# Supply_switch.net
KiCad netlist of a schematic drawn in EAGLE
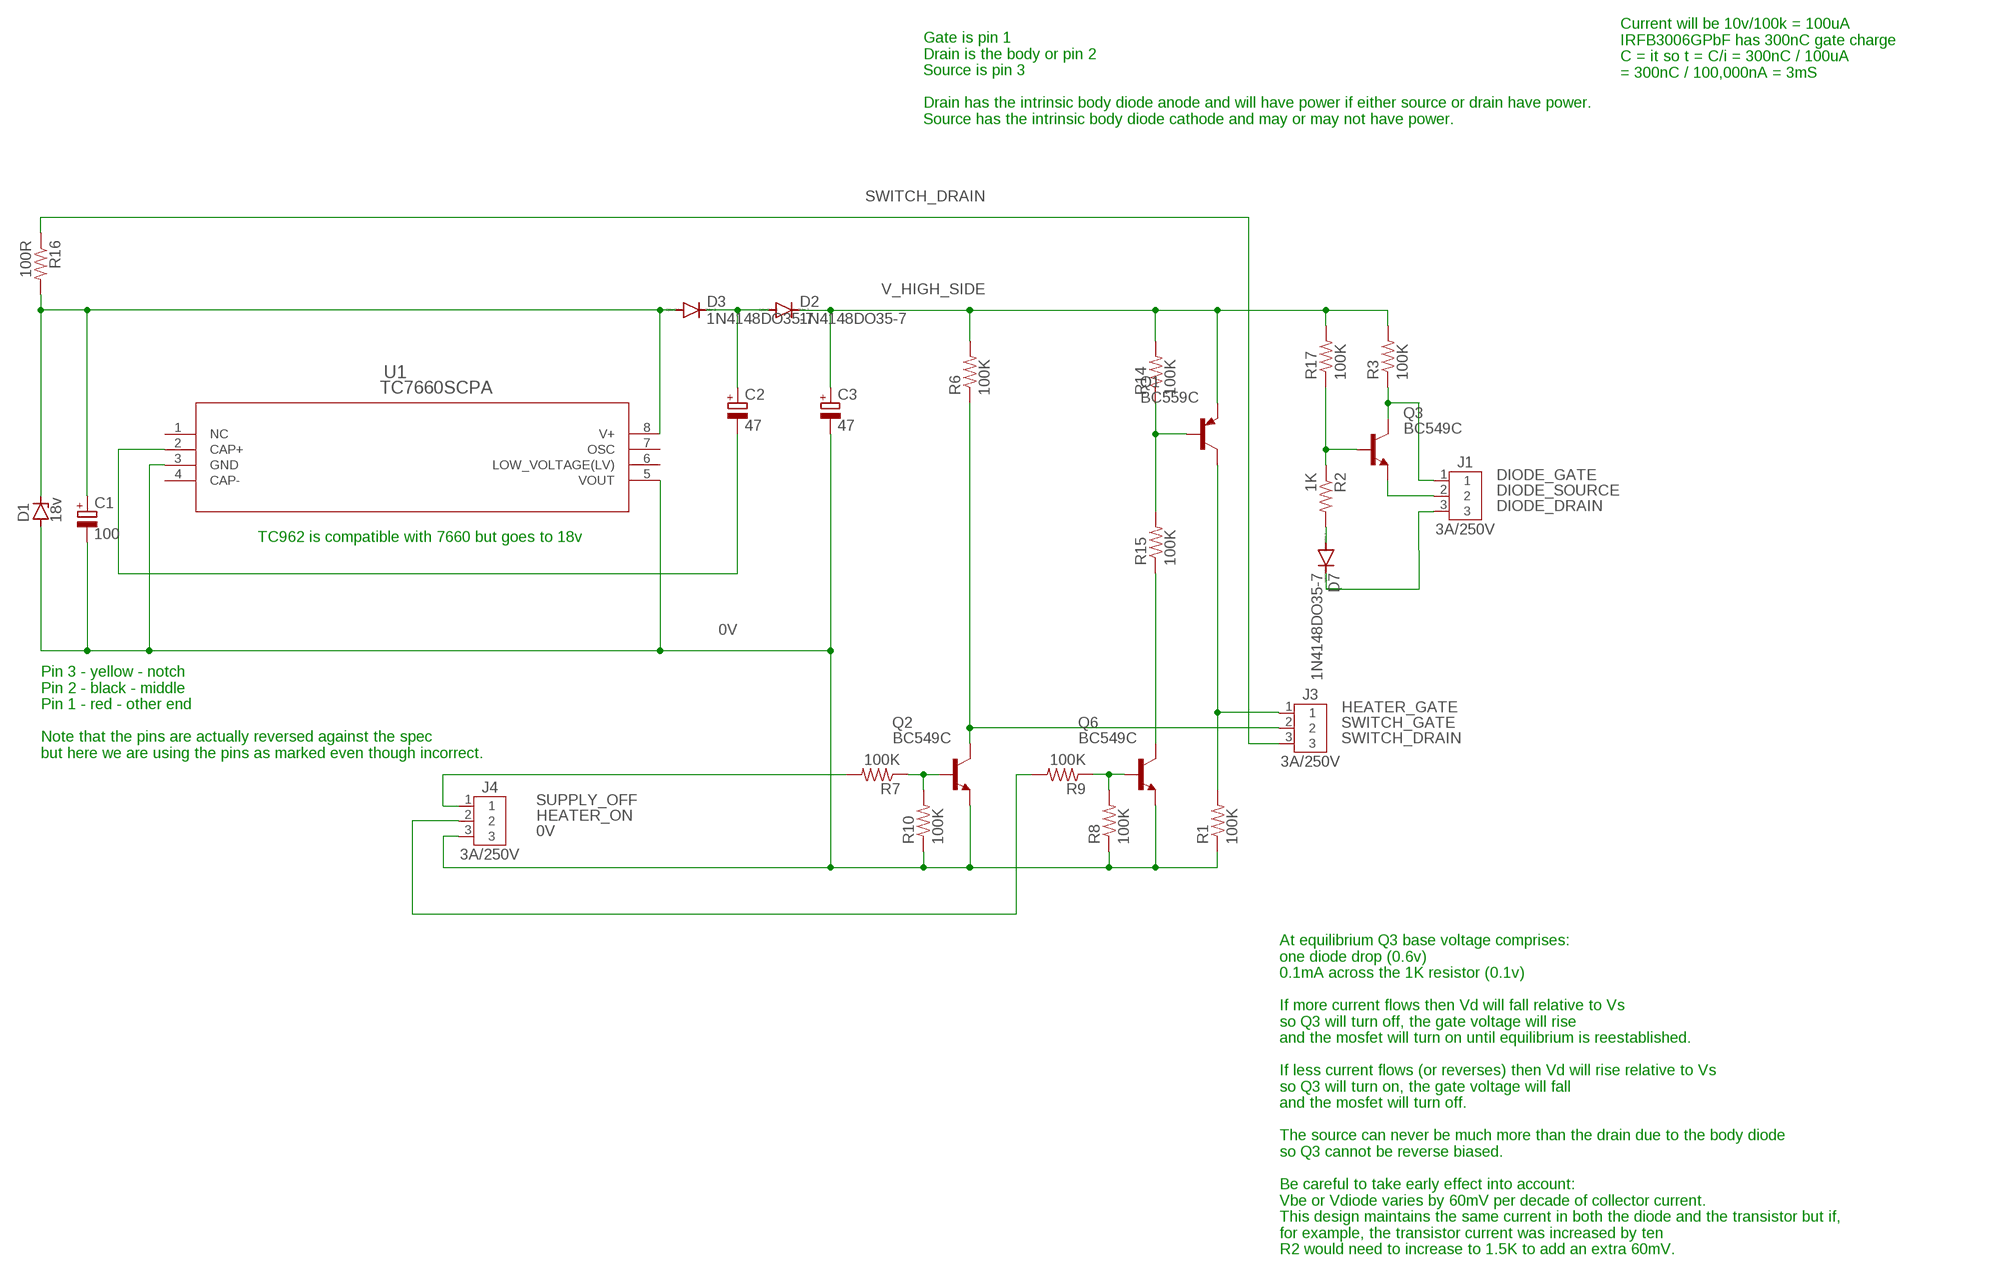
[diagram p0: schematic, sheet 1]

(export (version "E")
  (design (tool "Eeschema 10.0.6"))
  (components
    (comp (ref "C1")
      (value "100")
      (footprint "eagle-import:CAPPRD508W65D1000H1100B")
      (libsource (lib "eagle-import") (part "C-POLRADIAL-11MM-DIA_"))
    )
    (comp (ref "C2")
      (value "47")
      (footprint "eagle-import:CAPPRD508W65D1000H1100B")
      (libsource (lib "eagle-import") (part "C-POLRADIAL-11MM-DIA_"))
    )
    (comp (ref "C3")
      (value "47")
      (footprint "eagle-import:CAPPRD508W65D1000H1100B")
      (libsource (lib "eagle-import") (part "C-POLRADIAL-11MM-DIA_"))
    )
    (comp (ref "D1")
      (value "18v")
      (footprint "eagle-import:F126Z10")
      (libsource (lib "eagle-import") (part "ZENER-DIODEF126-10"))
    )
    (comp (ref "D2")
      (value "1N4148DO35-7")
      (footprint "eagle-import:DO35-7")
      (libsource (lib "eagle-import") (part "1N4148DO35-7"))
    )
    (comp (ref "D3")
      (value "1N4148DO35-7")
      (footprint "eagle-import:DO35-7")
      (libsource (lib "eagle-import") (part "1N4148DO35-7"))
    )
    (comp (ref "D7")
      (value "1N4148DO35-7")
      (footprint "eagle-import:DO35-7")
      (libsource (lib "eagle-import") (part "1N4148DO35-7"))
    )
    (comp (ref "J1")
      (value "3A/250V")
      (footprint "eagle-import:B3B-XH-A")
      (fields (field (name "MANUFACTURER") "JST (XH connector)") (field (name "MPN") "B3B-XH-A"))
      (libsource (lib "eagle-import") (part "B3B-XH-A"))
    )
    (comp (ref "J3")
      (value "3A/250V")
      (footprint "eagle-import:B3B-XH-A")
      (fields (field (name "MANUFACTURER") "JST (XH connector)") (field (name "MPN") "B3B-XH-A"))
      (libsource (lib "eagle-import") (part "B3B-XH-A"))
    )
    (comp (ref "J4")
      (value "3A/250V")
      (footprint "eagle-import:B3B-XH-A")
      (fields (field (name "MANUFACTURER") "JST (XH connector)") (field (name "MPN") "B3B-XH-A"))
      (libsource (lib "eagle-import") (part "B3B-XH-A"))
    )
    (comp (ref "Q1")
      (value "BC559C")
      (footprint "eagle-import:TO92-EBC")
      (libsource (lib "eagle-import") (part "BC559C"))
    )
    (comp (ref "Q2")
      (value "BC549C")
      (footprint "eagle-import:TO92-EBC")
      (libsource (lib "eagle-import") (part "BC549C"))
    )
    (comp (ref "Q3")
      (value "BC549C")
      (footprint "eagle-import:TO92-EBC")
      (libsource (lib "eagle-import") (part "BC549C"))
    )
    (comp (ref "Q6")
      (value "BC549C")
      (footprint "eagle-import:TO92-EBC")
      (libsource (lib "eagle-import") (part "BC549C"))
    )
    (comp (ref "R1")
      (value "100K")
      (footprint "eagle-import:0204_7")
      (libsource (lib "eagle-import") (part "RES_7"))
    )
    (comp (ref "R2")
      (value "1K")
      (footprint "eagle-import:0204_7")
      (libsource (lib "eagle-import") (part "RES_7"))
    )
    (comp (ref "R3")
      (value "100K")
      (footprint "eagle-import:0204_7")
      (libsource (lib "eagle-import") (part "RES_7"))
    )
    (comp (ref "R6")
      (value "100K")
      (footprint "eagle-import:0204_7")
      (libsource (lib "eagle-import") (part "RES_7"))
    )
    (comp (ref "R7")
      (value "100K")
      (footprint "eagle-import:0204_7")
      (libsource (lib "eagle-import") (part "RES_7"))
    )
    (comp (ref "R8")
      (value "100K")
      (footprint "eagle-import:0204_7")
      (libsource (lib "eagle-import") (part "RES_7"))
    )
    (comp (ref "R9")
      (value "100K")
      (footprint "eagle-import:0204_7")
      (libsource (lib "eagle-import") (part "RES_7"))
    )
    (comp (ref "R10")
      (value "100K")
      (footprint "eagle-import:0204_7")
      (libsource (lib "eagle-import") (part "RES_7"))
    )
    (comp (ref "R14")
      (value "100K")
      (footprint "eagle-import:0204_7")
      (libsource (lib "eagle-import") (part "RES_7"))
    )
    (comp (ref "R15")
      (value "100K")
      (footprint "eagle-import:0204_7")
      (libsource (lib "eagle-import") (part "RES_7"))
    )
    (comp (ref "R16")
      (value "100R")
      (footprint "eagle-import:0204_7")
      (libsource (lib "eagle-import") (part "RES_7"))
    )
    (comp (ref "R17")
      (value "100K")
      (footprint "eagle-import:0204_7")
      (libsource (lib "eagle-import") (part "RES_7"))
    )
    (comp (ref "U1")
      (value "TC7660SCPA")
      (footprint "eagle-import:PDIP8_300MC_MCH")
      (fields (field (name "COPYRIGHT") "Copyright (C) 2021 Ultra Librarian. All rights reserved."))
      (libsource (lib "eagle-import") (part "TC7660SCPA"))
    )
  )
  (nets
    (net (code "1") (name "/0V") (class "Default")
      (node (ref "C1") (pin "2") (pinfunction "-_2") (pintype "passive"))
      (node (ref "C3") (pin "2") (pinfunction "-_2") (pintype "passive"))
      (node (ref "D1") (pin "A") (pinfunction "A_A") (pintype "passive"))
      (node (ref "J4") (pin "3") (pinfunction "3_3") (pintype "bidirectional"))
      (node (ref "Q2") (pin "E") (pinfunction "E_E") (pintype "passive"))
      (node (ref "Q6") (pin "E") (pinfunction "E_E") (pintype "passive"))
      (node (ref "R1") (pin "1") (pinfunction "1_1") (pintype "passive"))
      (node (ref "R10") (pin "1") (pinfunction "1_1") (pintype "passive"))
      (node (ref "R8") (pin "1") (pinfunction "1_1") (pintype "passive"))
      (node (ref "U1") (pin "3") (pinfunction "GND_3") (pintype "passive"))
      (node (ref "U1") (pin "5") (pinfunction "VOUT_5") (pintype "output"))
    )
    (net (code "2") (name "/DIODE_DRAIN") (class "Default")
      (node (ref "D7") (pin "C") (pinfunction "C_C") (pintype "passive"))
      (node (ref "J1") (pin "3") (pinfunction "3_3") (pintype "bidirectional"))
    )
    (net (code "3") (name "/DIODE_GATE") (class "Default")
      (node (ref "J1") (pin "1") (pinfunction "1_1") (pintype "bidirectional"))
      (node (ref "Q3") (pin "C") (pinfunction "C_C") (pintype "passive"))
      (node (ref "R3") (pin "1") (pinfunction "1_1") (pintype "passive"))
    )
    (net (code "4") (name "/DIODE_SOURCE") (class "Default")
      (node (ref "J1") (pin "2") (pinfunction "2_2") (pintype "bidirectional"))
      (node (ref "Q3") (pin "E") (pinfunction "E_E") (pintype "passive"))
    )
    (net (code "5") (name "/HEATER_GATE") (class "Default")
      (node (ref "J3") (pin "1") (pinfunction "1_1") (pintype "bidirectional"))
      (node (ref "Q1") (pin "C") (pinfunction "C_C") (pintype "passive"))
      (node (ref "R1") (pin "2") (pinfunction "2_2") (pintype "passive"))
    )
    (net (code "6") (name "/HEATER_ON") (class "Default")
      (node (ref "J4") (pin "2") (pinfunction "2_2") (pintype "bidirectional"))
      (node (ref "R9") (pin "2") (pinfunction "2_2") (pintype "passive"))
    )
    (net (code "7") (name "/SUPPLY_OFF") (class "Default")
      (node (ref "J4") (pin "1") (pinfunction "1_1") (pintype "bidirectional"))
      (node (ref "R7") (pin "2") (pinfunction "2_2") (pintype "passive"))
    )
    (net (code "8") (name "/SWITCH_DRAIN") (class "Default")
      (node (ref "J3") (pin "3") (pinfunction "3_3") (pintype "bidirectional"))
      (node (ref "R16") (pin "1") (pinfunction "1_1") (pintype "passive"))
    )
    (net (code "9") (name "/SWITCH_GATE") (class "Default")
      (node (ref "J3") (pin "2") (pinfunction "2_2") (pintype "bidirectional"))
      (node (ref "Q2") (pin "C") (pinfunction "C_C") (pintype "passive"))
      (node (ref "R6") (pin "1") (pinfunction "1_1") (pintype "passive"))
    )
    (net (code "10") (name "/V_HIGH_SIDE") (class "Default")
      (node (ref "C3") (pin "1") (pinfunction "+_1") (pintype "passive"))
      (node (ref "D2") (pin "C") (pinfunction "C_C") (pintype "passive"))
      (node (ref "Q1") (pin "E") (pinfunction "E_E") (pintype "passive"))
      (node (ref "R14") (pin "2") (pinfunction "2_2") (pintype "passive"))
      (node (ref "R17") (pin "2") (pinfunction "2_2") (pintype "passive"))
      (node (ref "R3") (pin "2") (pinfunction "2_2") (pintype "passive"))
      (node (ref "R6") (pin "2") (pinfunction "2_2") (pintype "passive"))
    )
    (net (code "11") (name "Net-(C1-+)") (class "Default")
      (node (ref "C1") (pin "1") (pinfunction "+_1") (pintype "passive"))
      (node (ref "D1") (pin "C") (pinfunction "C_C") (pintype "passive"))
      (node (ref "D3") (pin "A") (pinfunction "A_A") (pintype "passive"))
      (node (ref "R16") (pin "2") (pinfunction "2_2") (pintype "passive"))
      (node (ref "U1") (pin "8") (pinfunction "V+_8") (pintype "passive"))
    )
    (net (code "12") (name "Net-(C2-+)") (class "Default")
      (node (ref "C2") (pin "1") (pinfunction "+_1") (pintype "passive"))
      (node (ref "D2") (pin "A") (pinfunction "A_A") (pintype "passive"))
      (node (ref "D3") (pin "C") (pinfunction "C_C") (pintype "passive"))
    )
    (net (code "13") (name "Net-(C2--)") (class "Default")
      (node (ref "C2") (pin "2") (pinfunction "-_2") (pintype "passive"))
      (node (ref "U1") (pin "2") (pinfunction "CAP+_2") (pintype "passive"))
    )
    (net (code "14") (name "Net-(D7-PadA)") (class "Default")
      (node (ref "D7") (pin "A") (pinfunction "A_A") (pintype "passive"))
      (node (ref "R2") (pin "2") (pinfunction "2_2") (pintype "passive"))
    )
    (net (code "15") (name "Net-(Q1-PadB)") (class "Default")
      (node (ref "Q1") (pin "B") (pinfunction "B_B") (pintype "passive"))
      (node (ref "R14") (pin "1") (pinfunction "1_1") (pintype "passive"))
      (node (ref "R15") (pin "2") (pinfunction "2_2") (pintype "passive"))
    )
    (net (code "16") (name "Net-(Q2-PadB)") (class "Default")
      (node (ref "Q2") (pin "B") (pinfunction "B_B") (pintype "passive"))
      (node (ref "R10") (pin "2") (pinfunction "2_2") (pintype "passive"))
      (node (ref "R7") (pin "1") (pinfunction "1_1") (pintype "passive"))
    )
    (net (code "17") (name "Net-(Q3-PadB)") (class "Default")
      (node (ref "Q3") (pin "B") (pinfunction "B_B") (pintype "passive"))
      (node (ref "R17") (pin "1") (pinfunction "1_1") (pintype "passive"))
      (node (ref "R2") (pin "1") (pinfunction "1_1") (pintype "passive"))
    )
    (net (code "18") (name "Net-(Q6-PadB)") (class "Default")
      (node (ref "Q6") (pin "B") (pinfunction "B_B") (pintype "passive"))
      (node (ref "R8") (pin "2") (pinfunction "2_2") (pintype "passive"))
      (node (ref "R9") (pin "1") (pinfunction "1_1") (pintype "passive"))
    )
    (net (code "19") (name "Net-(Q6-PadC)") (class "Default")
      (node (ref "Q6") (pin "C") (pinfunction "C_C") (pintype "passive"))
      (node (ref "R15") (pin "1") (pinfunction "1_1") (pintype "passive"))
    )
    (net (code "20") (name "unconnected-(U1-CAP--Pad4)") (class "Default")
      (node (ref "U1") (pin "4") (pinfunction "CAP-_4") (pintype "passive"))
    )
    (net (code "21") (name "unconnected-(U1-LOW_VOLTAGE(LV)-Pad6)") (class "Default")
      (node (ref "U1") (pin "6") (pinfunction "LOW_VOLTAGE(LV)_6") (pintype "passive"))
    )
    (net (code "22") (name "unconnected-(U1-NC-Pad1)") (class "Default")
      (node (ref "U1") (pin "1") (pinfunction "NC_1") (pintype "no_connect"))
    )
    (net (code "23") (name "unconnected-(U1-OSC-Pad7)") (class "Default")
      (node (ref "U1") (pin "7") (pinfunction "OSC_7") (pintype "input"))
    )
  )
)
